# HelvePicV1_0c.net
KiCad netlist of a schematic drawn in EAGLE
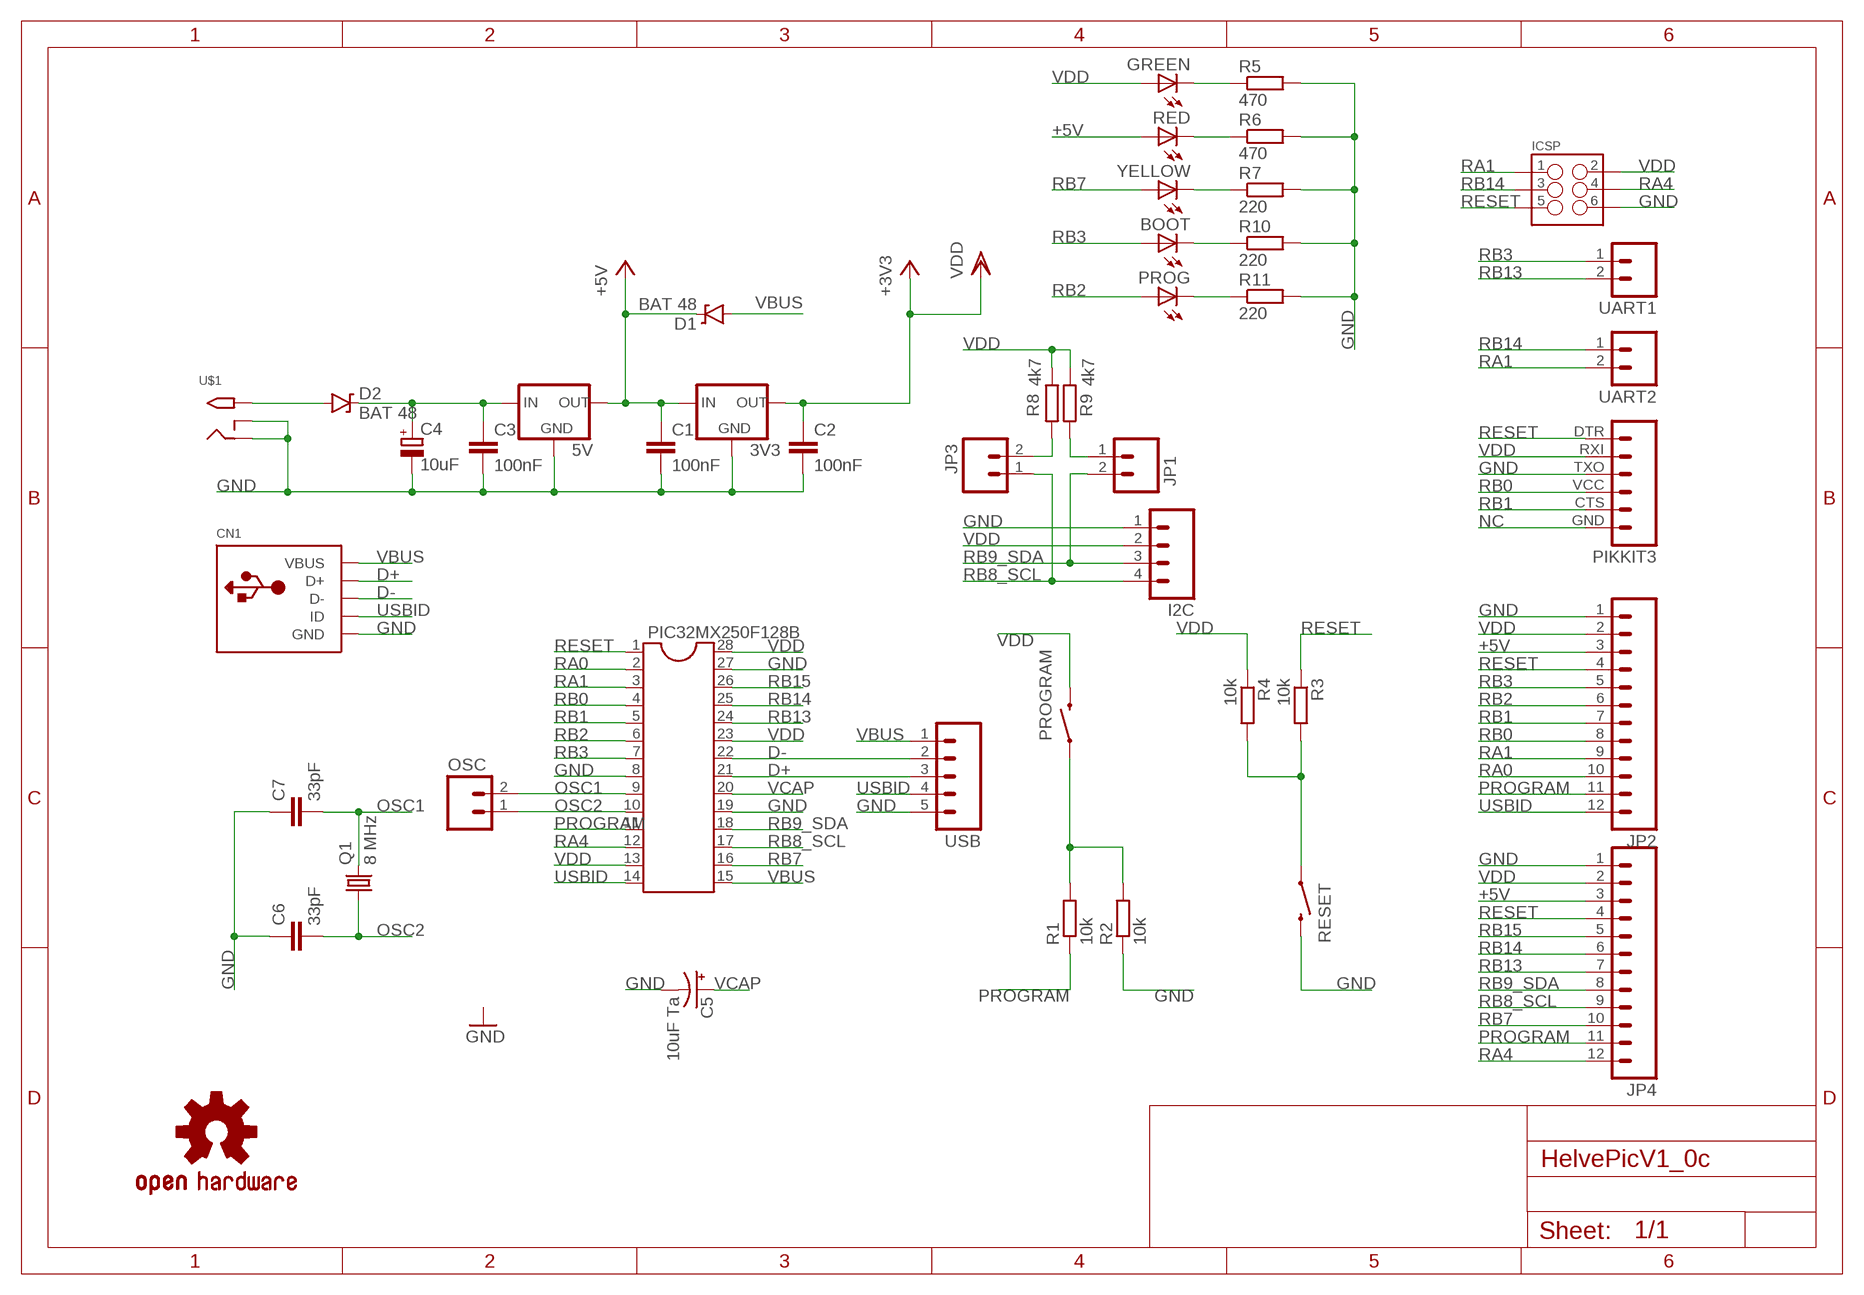
[diagram p0: schematic, sheet 1]

(export (version "E")
  (design (tool "Eeschema 10.0.6"))
  (components
    (comp (ref "3V3")
      (value "MCP1700INLINE")
      (footprint "eagle-import:TO92-INLINE")
      (libsource (lib "eagle-import") (part "MCP1700INLINE"))
    )
    (comp (ref "5V")
      (value "MCP1700INLINE")
      (footprint "eagle-import:TO92-INLINE")
      (libsource (lib "eagle-import") (part "MCP1700INLINE"))
    )
    (comp (ref "BOOT")
      (value "LED3MM")
      (footprint "eagle-import:LED3MM")
      (libsource (lib "eagle-import") (part "LED3MM"))
    )
    (comp (ref "C1")
      (value "100nF")
      (footprint "eagle-import:C025-030X050")
      (libsource (lib "eagle-import") (part "C-EU025-030X050"))
    )
    (comp (ref "C2")
      (value "100nF")
      (footprint "eagle-import:C025-030X050")
      (libsource (lib "eagle-import") (part "C-EU025-030X050"))
    )
    (comp (ref "C3")
      (value "100nF")
      (footprint "eagle-import:C025-030X050")
      (libsource (lib "eagle-import") (part "C-EU025-030X050"))
    )
    (comp (ref "C4")
      (value "10uF")
      (footprint "eagle-import:E5-6")
      (libsource (lib "eagle-import") (part "CPOL-EUE5-6"))
    )
    (comp (ref "C5")
      (value "10uF Ta")
      (footprint "eagle-import:CPOL-RADIAL-10UF-25V")
      (libsource (lib "eagle-import") (part "CAP_POLPTH2"))
    )
    (comp (ref "C6")
      (value "33pF")
      (footprint "eagle-import:C025-030X050")
      (libsource (lib "eagle-import") (part "C-EU025-030X050"))
    )
    (comp (ref "C7")
      (value "33pF")
      (footprint "eagle-import:C025-030X050")
      (libsource (lib "eagle-import") (part "C-EU025-030X050"))
    )
    (comp (ref "CN1")
      (value "USBMOLEX")
      (footprint "eagle-import:USB-MINIB-THM-MOLEX")
      (libsource (lib "eagle-import") (part "USBMOLEX"))
    )
    (comp (ref "D1")
      (value "BAT 48")
      (footprint "eagle-import:DIODE-ZENER")
      (libsource (lib "eagle-import") (part "DIODE-ZENERPTH"))
    )
    (comp (ref "D2")
      (value "BAT 48")
      (footprint "eagle-import:DIODE-ZENER")
      (libsource (lib "eagle-import") (part "DIODE-ZENERPTH"))
    )
    (comp (ref "GREEN")
      (value "LED3MM")
      (footprint "eagle-import:LED3MM")
      (libsource (lib "eagle-import") (part "LED3MM"))
    )
    (comp (ref "I2C")
      (value "M04PTH")
      (footprint "eagle-import:1X04")
      (libsource (lib "eagle-import") (part "M04PTH"))
    )
    (comp (ref "ICSP")
      (value "M03X22X3_SILK_SM")
      (footprint "eagle-import:2X3")
      (libsource (lib "eagle-import") (part "M03X22X3_SILK_SM"))
    )
    (comp (ref "JP1")
      (value "M02PTH")
      (footprint "eagle-import:1X02")
      (libsource (lib "eagle-import") (part "M02PTH"))
    )
    (comp (ref "JP2")
      (value "M12PTH")
      (footprint "eagle-import:1X12")
      (libsource (lib "eagle-import") (part "M12PTH"))
    )
    (comp (ref "JP3")
      (value "M02PTH")
      (footprint "eagle-import:1X02")
      (libsource (lib "eagle-import") (part "M02PTH"))
    )
    (comp (ref "JP4")
      (value "M12PTH")
      (footprint "eagle-import:1X12")
      (libsource (lib "eagle-import") (part "M12PTH"))
    )
    (comp (ref "LOGO1")
      (value "OSHW-LOGOS")
      (footprint "eagle-import:OSHW-LOGO-S")
      (libsource (lib "eagle-import") (part "OSHW-LOGOS"))
    )
    (comp (ref "OSC")
      (value "M02PTH")
      (footprint "eagle-import:1X02")
      (libsource (lib "eagle-import") (part "M02PTH"))
    )
    (comp (ref "PIC32MX250F128B")
      (value "DIL28-3")
      (footprint "eagle-import:DIL28-3")
      (libsource (lib "eagle-import") (part "DIL28-3"))
    )
    (comp (ref "PIKKIT3")
      (value "M06SIP")
      (footprint "eagle-import:1X06")
      (libsource (lib "eagle-import") (part "M06SIP"))
    )
    (comp (ref "PROG")
      (value "LED3MM")
      (footprint "eagle-import:LED3MM")
      (libsource (lib "eagle-import") (part "LED3MM"))
    )
    (comp (ref "PROGRAM")
      (value "SWITCH-MOMENTARY-2PTH")
      (footprint "eagle-import:TACTILE-PTH")
      (libsource (lib "eagle-import") (part "SWITCH-MOMENTARY-2PTH"))
    )
    (comp (ref "Q1")
      (value "8 MHz")
      (footprint "eagle-import:HC49U-V")
      (libsource (lib "eagle-import") (part "CRYSTALHC49U-V"))
    )
    (comp (ref "R1")
      (value "10k")
      (footprint "eagle-import:0207_7")
      (libsource (lib "eagle-import") (part "R-EU_0207/7"))
    )
    (comp (ref "R2")
      (value "10k")
      (footprint "eagle-import:0207_7")
      (libsource (lib "eagle-import") (part "R-EU_0207/7"))
    )
    (comp (ref "R3")
      (value "10k")
      (footprint "eagle-import:0207_7")
      (libsource (lib "eagle-import") (part "R-EU_0207/7"))
    )
    (comp (ref "R4")
      (value "10k")
      (footprint "eagle-import:0207_7")
      (libsource (lib "eagle-import") (part "R-EU_0207/7"))
    )
    (comp (ref "R5")
      (value "470")
      (footprint "eagle-import:0207_7")
      (libsource (lib "eagle-import") (part "R-EU_0207/7"))
    )
    (comp (ref "R6")
      (value "470")
      (footprint "eagle-import:0207_7")
      (libsource (lib "eagle-import") (part "R-EU_0207/7"))
    )
    (comp (ref "R7")
      (value "220")
      (footprint "eagle-import:0207_7")
      (libsource (lib "eagle-import") (part "R-EU_0207/7"))
    )
    (comp (ref "R8")
      (value "4k7")
      (footprint "eagle-import:0207_7")
      (libsource (lib "eagle-import") (part "R-EU_0207/7"))
    )
    (comp (ref "R9")
      (value "4k7")
      (footprint "eagle-import:0207_7")
      (libsource (lib "eagle-import") (part "R-EU_0207/7"))
    )
    (comp (ref "R10")
      (value "220")
      (footprint "eagle-import:0207_7")
      (libsource (lib "eagle-import") (part "R-EU_0207/7"))
    )
    (comp (ref "R11")
      (value "220")
      (footprint "eagle-import:0207_7")
      (libsource (lib "eagle-import") (part "R-EU_0207/7"))
    )
    (comp (ref "RED")
      (value "LED3MM")
      (footprint "eagle-import:LED3MM")
      (libsource (lib "eagle-import") (part "LED3MM"))
    )
    (comp (ref "RESET")
      (value "SWITCH-MOMENTARY-2PTH")
      (footprint "eagle-import:TACTILE-PTH")
      (libsource (lib "eagle-import") (part "SWITCH-MOMENTARY-2PTH"))
    )
    (comp (ref "U$1")
      (value "2.1MMJACKTHM")
      (footprint "eagle-import:PJ-102A")
      (libsource (lib "eagle-import") (part "2.1MMJACKTHM"))
    )
    (comp (ref "UART1")
      (value "M02PTH")
      (footprint "eagle-import:1X02")
      (libsource (lib "eagle-import") (part "M02PTH"))
    )
    (comp (ref "UART2")
      (value "M02PTH")
      (footprint "eagle-import:1X02")
      (libsource (lib "eagle-import") (part "M02PTH"))
    )
    (comp (ref "USB")
      (value "M05PTH")
      (footprint "eagle-import:1X05")
      (libsource (lib "eagle-import") (part "M05PTH"))
    )
    (comp (ref "YELLOW")
      (value "LED3MM")
      (footprint "eagle-import:LED3MM")
      (libsource (lib "eagle-import") (part "LED3MM"))
    )
  )
  (nets
    (net (code "1") (name "+3V3") (class "Default")
      (node (ref "3V3") (pin "3") (pinfunction "OUT_3") (pintype "passive"))
      (node (ref "C2") (pin "1") (pinfunction "1_1") (pintype "passive"))
      (node (ref "GREEN") (pin "A") (pinfunction "A_A") (pintype "passive"))
      (node (ref "I2C") (pin "2") (pinfunction "2_2") (pintype "passive"))
      (node (ref "ICSP") (pin "2") (pinfunction "2_2") (pintype "bidirectional"))
      (node (ref "JP2") (pin "2") (pinfunction "2_2") (pintype "passive"))
      (node (ref "JP4") (pin "2") (pinfunction "2_2") (pintype "passive"))
      (node (ref "PIC32MX250F128B") (pin "13") (pinfunction "13_13") (pintype "passive"))
      (node (ref "PIC32MX250F128B") (pin "23") (pinfunction "23_23") (pintype "passive"))
      (node (ref "PIC32MX250F128B") (pin "28") (pinfunction "28_28") (pintype "passive"))
      (node (ref "PIKKIT3") (pin "RXI") (pinfunction "2_RXI") (pintype "passive"))
      (node (ref "PROGRAM") (pin "3") (pinfunction "2_3") (pintype "passive"))
      (node (ref "R4") (pin "1") (pinfunction "1_1") (pintype "passive"))
      (node (ref "R8") (pin "1") (pinfunction "1_1") (pintype "passive"))
      (node (ref "R9") (pin "1") (pinfunction "1_1") (pintype "passive"))
    )
    (net (code "2") (name "+5V") (class "Default")
      (node (ref "3V3") (pin "2") (pinfunction "IN_2") (pintype "input"))
      (node (ref "5V") (pin "3") (pinfunction "OUT_3") (pintype "passive"))
      (node (ref "C1") (pin "1") (pinfunction "1_1") (pintype "passive"))
      (node (ref "D1") (pin "P$1") (pinfunction "C_P$1") (pintype "passive"))
      (node (ref "JP2") (pin "3") (pinfunction "3_3") (pintype "passive"))
      (node (ref "JP4") (pin "3") (pinfunction "3_3") (pintype "passive"))
      (node (ref "RED") (pin "A") (pinfunction "A_A") (pintype "passive"))
    )
    (net (code "3") (name "/D+") (class "Default")
      (node (ref "CN1") (pin "D+") (pinfunction "D+_D+") (pintype "bidirectional"))
      (node (ref "PIC32MX250F128B") (pin "21") (pinfunction "21_21") (pintype "passive"))
      (node (ref "USB") (pin "3") (pinfunction "3_3") (pintype "passive"))
    )
    (net (code "4") (name "/D-") (class "Default")
      (node (ref "CN1") (pin "D-") (pinfunction "D-_D-") (pintype "bidirectional"))
      (node (ref "PIC32MX250F128B") (pin "22") (pinfunction "22_22") (pintype "passive"))
      (node (ref "USB") (pin "2") (pinfunction "2_2") (pintype "passive"))
    )
    (net (code "5") (name "/NC") (class "Default")
      (node (ref "PIKKIT3") (pin "GND") (pinfunction "6_GND") (pintype "passive"))
    )
    (net (code "6") (name "/OSC1") (class "Default")
      (node (ref "C7") (pin "2") (pinfunction "2_2") (pintype "passive"))
      (node (ref "OSC") (pin "2") (pinfunction "2_2") (pintype "passive"))
      (node (ref "PIC32MX250F128B") (pin "9") (pinfunction "9_9") (pintype "passive"))
      (node (ref "Q1") (pin "2") (pinfunction "2_2") (pintype "passive"))
    )
    (net (code "7") (name "/OSC2") (class "Default")
      (node (ref "C6") (pin "2") (pinfunction "2_2") (pintype "passive"))
      (node (ref "OSC") (pin "1") (pinfunction "1_1") (pintype "passive"))
      (node (ref "PIC32MX250F128B") (pin "10") (pinfunction "10_10") (pintype "passive"))
      (node (ref "Q1") (pin "1") (pinfunction "1_1") (pintype "passive"))
    )
    (net (code "8") (name "/PROGRAM") (class "Default")
      (node (ref "JP2") (pin "11") (pinfunction "11_11") (pintype "passive"))
      (node (ref "JP4") (pin "11") (pinfunction "11_11") (pintype "passive"))
      (node (ref "PIC32MX250F128B") (pin "11") (pinfunction "11_11") (pintype "passive"))
      (node (ref "R1") (pin "1") (pinfunction "1_1") (pintype "passive"))
    )
    (net (code "9") (name "/RA0") (class "Default")
      (node (ref "JP2") (pin "10") (pinfunction "10_10") (pintype "passive"))
      (node (ref "PIC32MX250F128B") (pin "2") (pinfunction "2_2") (pintype "passive"))
    )
    (net (code "10") (name "/RA1") (class "Default")
      (node (ref "ICSP") (pin "1") (pinfunction "1_1") (pintype "bidirectional"))
      (node (ref "JP2") (pin "9") (pinfunction "9_9") (pintype "passive"))
      (node (ref "PIC32MX250F128B") (pin "3") (pinfunction "3_3") (pintype "passive"))
      (node (ref "UART2") (pin "2") (pinfunction "2_2") (pintype "passive"))
    )
    (net (code "11") (name "/RA4") (class "Default")
      (node (ref "ICSP") (pin "4") (pinfunction "4_4") (pintype "bidirectional"))
      (node (ref "JP4") (pin "12") (pinfunction "12_12") (pintype "passive"))
      (node (ref "PIC32MX250F128B") (pin "12") (pinfunction "12_12") (pintype "passive"))
    )
    (net (code "12") (name "/RB0") (class "Default")
      (node (ref "JP2") (pin "8") (pinfunction "8_8") (pintype "passive"))
      (node (ref "PIC32MX250F128B") (pin "4") (pinfunction "4_4") (pintype "passive"))
      (node (ref "PIKKIT3") (pin "VCC") (pinfunction "4_VCC") (pintype "passive"))
    )
    (net (code "13") (name "/RB1") (class "Default")
      (node (ref "JP2") (pin "7") (pinfunction "7_7") (pintype "passive"))
      (node (ref "PIC32MX250F128B") (pin "5") (pinfunction "5_5") (pintype "passive"))
      (node (ref "PIKKIT3") (pin "CTS") (pinfunction "5_CTS") (pintype "passive"))
    )
    (net (code "14") (name "/RB2") (class "Default")
      (node (ref "JP2") (pin "6") (pinfunction "6_6") (pintype "passive"))
      (node (ref "PIC32MX250F128B") (pin "6") (pinfunction "6_6") (pintype "passive"))
      (node (ref "PROG") (pin "A") (pinfunction "A_A") (pintype "passive"))
    )
    (net (code "15") (name "/RB3") (class "Default")
      (node (ref "BOOT") (pin "A") (pinfunction "A_A") (pintype "passive"))
      (node (ref "JP2") (pin "5") (pinfunction "5_5") (pintype "passive"))
      (node (ref "PIC32MX250F128B") (pin "7") (pinfunction "7_7") (pintype "passive"))
      (node (ref "UART1") (pin "1") (pinfunction "1_1") (pintype "passive"))
    )
    (net (code "16") (name "/RB7") (class "Default")
      (node (ref "JP4") (pin "10") (pinfunction "10_10") (pintype "passive"))
      (node (ref "PIC32MX250F128B") (pin "16") (pinfunction "16_16") (pintype "passive"))
      (node (ref "YELLOW") (pin "A") (pinfunction "A_A") (pintype "passive"))
    )
    (net (code "17") (name "/RB8_SCL") (class "Default")
      (node (ref "I2C") (pin "4") (pinfunction "4_4") (pintype "passive"))
      (node (ref "JP3") (pin "1") (pinfunction "1_1") (pintype "passive"))
      (node (ref "JP4") (pin "9") (pinfunction "9_9") (pintype "passive"))
      (node (ref "PIC32MX250F128B") (pin "17") (pinfunction "17_17") (pintype "passive"))
    )
    (net (code "18") (name "/RB9_SDA") (class "Default")
      (node (ref "I2C") (pin "3") (pinfunction "3_3") (pintype "passive"))
      (node (ref "JP1") (pin "2") (pinfunction "2_2") (pintype "passive"))
      (node (ref "JP4") (pin "8") (pinfunction "8_8") (pintype "passive"))
      (node (ref "PIC32MX250F128B") (pin "18") (pinfunction "18_18") (pintype "passive"))
    )
    (net (code "19") (name "/RB13") (class "Default")
      (node (ref "JP4") (pin "7") (pinfunction "7_7") (pintype "passive"))
      (node (ref "PIC32MX250F128B") (pin "24") (pinfunction "24_24") (pintype "passive"))
      (node (ref "UART1") (pin "2") (pinfunction "2_2") (pintype "passive"))
    )
    (net (code "20") (name "/RB14") (class "Default")
      (node (ref "ICSP") (pin "3") (pinfunction "3_3") (pintype "bidirectional"))
      (node (ref "JP4") (pin "6") (pinfunction "6_6") (pintype "passive"))
      (node (ref "PIC32MX250F128B") (pin "25") (pinfunction "25_25") (pintype "passive"))
      (node (ref "UART2") (pin "1") (pinfunction "1_1") (pintype "passive"))
    )
    (net (code "21") (name "/RB15") (class "Default")
      (node (ref "JP4") (pin "5") (pinfunction "5_5") (pintype "passive"))
      (node (ref "PIC32MX250F128B") (pin "26") (pinfunction "26_26") (pintype "passive"))
    )
    (net (code "22") (name "/RESET") (class "Default")
      (node (ref "ICSP") (pin "5") (pinfunction "5_5") (pintype "bidirectional"))
      (node (ref "JP2") (pin "4") (pinfunction "4_4") (pintype "passive"))
      (node (ref "JP4") (pin "4") (pinfunction "4_4") (pintype "passive"))
      (node (ref "PIC32MX250F128B") (pin "1") (pinfunction "1_1") (pintype "passive"))
      (node (ref "PIKKIT3") (pin "DTR") (pinfunction "1_DTR") (pintype "passive"))
      (node (ref "R3") (pin "1") (pinfunction "1_1") (pintype "passive"))
    )
    (net (code "23") (name "/USBID") (class "Default")
      (node (ref "CN1") (pin "ID") (pinfunction "ID_ID") (pintype "bidirectional"))
      (node (ref "JP2") (pin "12") (pinfunction "12_12") (pintype "passive"))
      (node (ref "PIC32MX250F128B") (pin "14") (pinfunction "14_14") (pintype "passive"))
      (node (ref "USB") (pin "4") (pinfunction "4_4") (pintype "passive"))
    )
    (net (code "24") (name "/VBUS") (class "Default")
      (node (ref "CN1") (pin "VBUS") (pinfunction "VBUS_VBUS") (pintype "power_in"))
      (node (ref "D1") (pin "P$2") (pinfunction "A_P$2") (pintype "passive"))
      (node (ref "PIC32MX250F128B") (pin "15") (pinfunction "15_15") (pintype "passive"))
      (node (ref "USB") (pin "1") (pinfunction "1_1") (pintype "passive"))
    )
    (net (code "25") (name "/VCAP") (class "Default")
      (node (ref "C5") (pin "1") (pinfunction "+_1") (pintype "passive"))
      (node (ref "PIC32MX250F128B") (pin "20") (pinfunction "20_20") (pintype "passive"))
    )
    (net (code "26") (name "GND") (class "Default")
      (node (ref "3V3") (pin "1") (pinfunction "GND_1") (pintype "input"))
      (node (ref "5V") (pin "1") (pinfunction "GND_1") (pintype "input"))
      (node (ref "C1") (pin "2") (pinfunction "2_2") (pintype "passive"))
      (node (ref "C2") (pin "2") (pinfunction "2_2") (pintype "passive"))
      (node (ref "C3") (pin "2") (pinfunction "2_2") (pintype "passive"))
      (node (ref "C4") (pin "-") (pinfunction "-_-") (pintype "passive"))
      (node (ref "C5") (pin "2") (pinfunction "-_2") (pintype "passive"))
      (node (ref "C6") (pin "1") (pinfunction "1_1") (pintype "passive"))
      (node (ref "C7") (pin "1") (pinfunction "1_1") (pintype "passive"))
      (node (ref "CN1") (pin "GND") (pinfunction "GND_GND") (pintype "power_in"))
      (node (ref "I2C") (pin "1") (pinfunction "1_1") (pintype "passive"))
      (node (ref "ICSP") (pin "6") (pinfunction "6_6") (pintype "bidirectional"))
      (node (ref "JP2") (pin "1") (pinfunction "1_1") (pintype "passive"))
      (node (ref "JP4") (pin "1") (pinfunction "1_1") (pintype "passive"))
      (node (ref "PIC32MX250F128B") (pin "19") (pinfunction "19_19") (pintype "passive"))
      (node (ref "PIC32MX250F128B") (pin "27") (pinfunction "27_27") (pintype "passive"))
      (node (ref "PIC32MX250F128B") (pin "8") (pinfunction "8_8") (pintype "passive"))
      (node (ref "PIKKIT3") (pin "TXO") (pinfunction "3_TXO") (pintype "passive"))
      (node (ref "R10") (pin "2") (pinfunction "2_2") (pintype "passive"))
      (node (ref "R11") (pin "2") (pinfunction "2_2") (pintype "passive"))
      (node (ref "R2") (pin "1") (pinfunction "1_1") (pintype "passive"))
      (node (ref "R5") (pin "2") (pinfunction "2_2") (pintype "passive"))
      (node (ref "R6") (pin "2") (pinfunction "2_2") (pintype "passive"))
      (node (ref "R7") (pin "2") (pinfunction "2_2") (pintype "passive"))
      (node (ref "RESET") (pin "3") (pinfunction "2_3") (pintype "passive"))
      (node (ref "U$1") (pin "RING") (pinfunction "RING_RING") (pintype "bidirectional"))
      (node (ref "U$1") (pin "RING_SW") (pinfunction "RING_SW_RING_SW") (pintype "bidirectional"))
      (node (ref "USB") (pin "5") (pinfunction "5_5") (pintype "passive"))
    )
    (net (code "27") (name "Net-(5V-IN)") (class "Default")
      (node (ref "5V") (pin "2") (pinfunction "IN_2") (pintype "input"))
      (node (ref "C3") (pin "1") (pinfunction "1_1") (pintype "passive"))
      (node (ref "C4") (pin "+") (pinfunction "+_+") (pintype "passive"))
      (node (ref "D2") (pin "P$1") (pinfunction "C_P$1") (pintype "passive"))
    )
    (net (code "28") (name "Net-(BOOT-C)") (class "Default")
      (node (ref "BOOT") (pin "K") (pinfunction "C_K") (pintype "passive"))
      (node (ref "R10") (pin "1") (pinfunction "1_1") (pintype "passive"))
    )
    (net (code "29") (name "Net-(D2-A)") (class "Default")
      (node (ref "D2") (pin "P$2") (pinfunction "A_P$2") (pintype "passive"))
      (node (ref "U$1") (pin "TIP") (pinfunction "TIP_TIP") (pintype "bidirectional"))
    )
    (net (code "30") (name "Net-(GREEN-C)") (class "Default")
      (node (ref "GREEN") (pin "K") (pinfunction "C_K") (pintype "passive"))
      (node (ref "R5") (pin "1") (pinfunction "1_1") (pintype "passive"))
    )
    (net (code "31") (name "Net-(JP1-Pad1)") (class "Default")
      (node (ref "JP1") (pin "1") (pinfunction "1_1") (pintype "passive"))
      (node (ref "R9") (pin "2") (pinfunction "2_2") (pintype "passive"))
    )
    (net (code "32") (name "Net-(JP3-Pad2)") (class "Default")
      (node (ref "JP3") (pin "2") (pinfunction "2_2") (pintype "passive"))
      (node (ref "R8") (pin "2") (pinfunction "2_2") (pintype "passive"))
    )
    (net (code "33") (name "Net-(PROG-C)") (class "Default")
      (node (ref "PROG") (pin "K") (pinfunction "C_K") (pintype "passive"))
      (node (ref "R11") (pin "1") (pinfunction "1_1") (pintype "passive"))
    )
    (net (code "34") (name "Net-(PROGRAM-Pad1)") (class "Default")
      (node (ref "PROGRAM") (pin "1") (pinfunction "1_1") (pintype "passive"))
      (node (ref "R1") (pin "2") (pinfunction "2_2") (pintype "passive"))
      (node (ref "R2") (pin "2") (pinfunction "2_2") (pintype "passive"))
    )
    (net (code "35") (name "Net-(R3-Pad2)") (class "Default")
      (node (ref "R3") (pin "2") (pinfunction "2_2") (pintype "passive"))
      (node (ref "R4") (pin "2") (pinfunction "2_2") (pintype "passive"))
      (node (ref "RESET") (pin "1") (pinfunction "1_1") (pintype "passive"))
    )
    (net (code "36") (name "Net-(RED-C)") (class "Default")
      (node (ref "R6") (pin "1") (pinfunction "1_1") (pintype "passive"))
      (node (ref "RED") (pin "K") (pinfunction "C_K") (pintype "passive"))
    )
    (net (code "37") (name "Net-(YELLOW-C)") (class "Default")
      (node (ref "R7") (pin "1") (pinfunction "1_1") (pintype "passive"))
      (node (ref "YELLOW") (pin "K") (pinfunction "C_K") (pintype "passive"))
    )
  )
)
